# wifilamp2.net
KiCad netlist of a schematic drawn in EAGLE
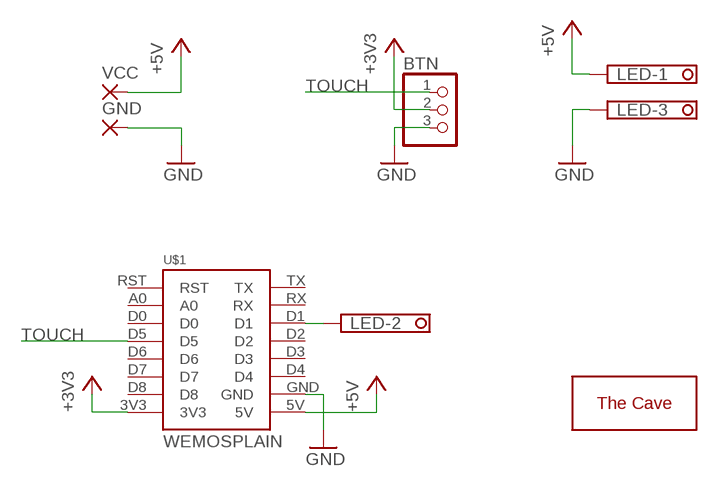
[diagram p0: schematic, sheet 1]

(export (version "E")
  (design (tool "Eeschema 10.0.6"))
  (components
    (comp (ref "BTN")
      (value "PINHD-1X3")
      (footprint "eagle-import:1X03")
      (libsource (lib "eagle-import") (part "PINHD-1X3"))
    )
    (comp (ref "GND")
      (value "WIREPAD3,81/1,4")
      (footprint "eagle-import:3,81_1,4")
      (libsource (lib "eagle-import") (part "WIREPAD3,81/1,4"))
    )
    (comp (ref "LED")
      (value "1751251")
      (footprint "eagle-import:1751251")
      (libsource (lib "eagle-import") (part "1751251"))
    )
    (comp (ref "U$1")
      (value "WEMOSPLAIN")
      (footprint "eagle-import:WEMOS-PLAIN")
      (libsource (lib "eagle-import") (part "WEMOSPLAIN"))
    )
    (comp (ref "U$2")
      (value "THECAVE_LOGO_TOP_SMALL")
      (footprint "eagle-import:LOGO_TOP_SMALL")
      (libsource (lib "eagle-import") (part "THECAVE_LOGO_TOP_SMALL"))
    )
    (comp (ref "VCC")
      (value "PAD3,81/2")
      (footprint "eagle-import:PAD3,81_2")
      (libsource (lib "eagle-import") (part "PAD3,81/2"))
    )
  )
  (nets
    (net (code "1") (name "+3V3") (class "Default")
      (node (ref "BTN") (pin "2") (pinfunction "2_2") (pintype "passive"))
      (node (ref "U$1") (pin "3V3") (pinfunction "3V3_3V3") (pintype "bidirectional"))
    )
    (net (code "2") (name "+5V") (class "Default")
      (node (ref "LED") (pin "1") (pinfunction "K_1") (pintype "passive"))
      (node (ref "U$1") (pin "5V") (pinfunction "5V_5V") (pintype "bidirectional"))
      (node (ref "VCC") (pin "1") (pinfunction "P_1") (pintype "passive"))
    )
    (net (code "3") (name "/TOUCH") (class "Default")
      (node (ref "BTN") (pin "1") (pinfunction "1_1") (pintype "passive"))
      (node (ref "U$1") (pin "D5") (pinfunction "D5_D5") (pintype "bidirectional"))
    )
    (net (code "4") (name "GND") (class "Default")
      (node (ref "BTN") (pin "3") (pinfunction "3_3") (pintype "passive"))
      (node (ref "GND") (pin "1") (pinfunction "P_1") (pintype "passive"))
      (node (ref "LED") (pin "3") (pinfunction "K_3") (pintype "passive"))
      (node (ref "U$1") (pin "GND") (pinfunction "GND_GND") (pintype "bidirectional"))
    )
    (net (code "5") (name "Net-(LEDB-K)") (class "Default")
      (node (ref "LED") (pin "2") (pinfunction "K_2") (pintype "passive"))
      (node (ref "U$1") (pin "D1") (pinfunction "D1_D1") (pintype "bidirectional"))
    )
    (net (code "6") (name "unconnected-(U$1-PadA0)") (class "Default")
      (node (ref "U$1") (pin "A0") (pinfunction "A0_A0") (pintype "bidirectional"))
    )
    (net (code "7") (name "unconnected-(U$1-PadD0)") (class "Default")
      (node (ref "U$1") (pin "D0") (pinfunction "D0_D0") (pintype "bidirectional"))
    )
    (net (code "8") (name "unconnected-(U$1-PadD2)") (class "Default")
      (node (ref "U$1") (pin "D2") (pinfunction "D2_D2") (pintype "bidirectional"))
    )
    (net (code "9") (name "unconnected-(U$1-PadD3)") (class "Default")
      (node (ref "U$1") (pin "D3") (pinfunction "D3_D3") (pintype "bidirectional"))
    )
    (net (code "10") (name "unconnected-(U$1-PadD4)") (class "Default")
      (node (ref "U$1") (pin "D4") (pinfunction "D4_D4") (pintype "bidirectional"))
    )
    (net (code "11") (name "unconnected-(U$1-PadD6)") (class "Default")
      (node (ref "U$1") (pin "D6") (pinfunction "D6_D6") (pintype "bidirectional"))
    )
    (net (code "12") (name "unconnected-(U$1-PadD7)") (class "Default")
      (node (ref "U$1") (pin "D7") (pinfunction "D7_D7") (pintype "bidirectional"))
    )
    (net (code "13") (name "unconnected-(U$1-PadD8)") (class "Default")
      (node (ref "U$1") (pin "D8") (pinfunction "D8_D8") (pintype "bidirectional"))
    )
    (net (code "14") (name "unconnected-(U$1-PadRST)") (class "Default")
      (node (ref "U$1") (pin "RST") (pinfunction "RST_RST") (pintype "bidirectional"))
    )
    (net (code "15") (name "unconnected-(U$1-PadRX)") (class "Default")
      (node (ref "U$1") (pin "RX") (pinfunction "RX_RX") (pintype "bidirectional"))
    )
    (net (code "16") (name "unconnected-(U$1-PadTX)") (class "Default")
      (node (ref "U$1") (pin "TX") (pinfunction "TX_TX") (pintype "bidirectional"))
    )
  )
)
